# USART_IrDA.net
KiCad netlist of a schematic drawn in Altium Designer
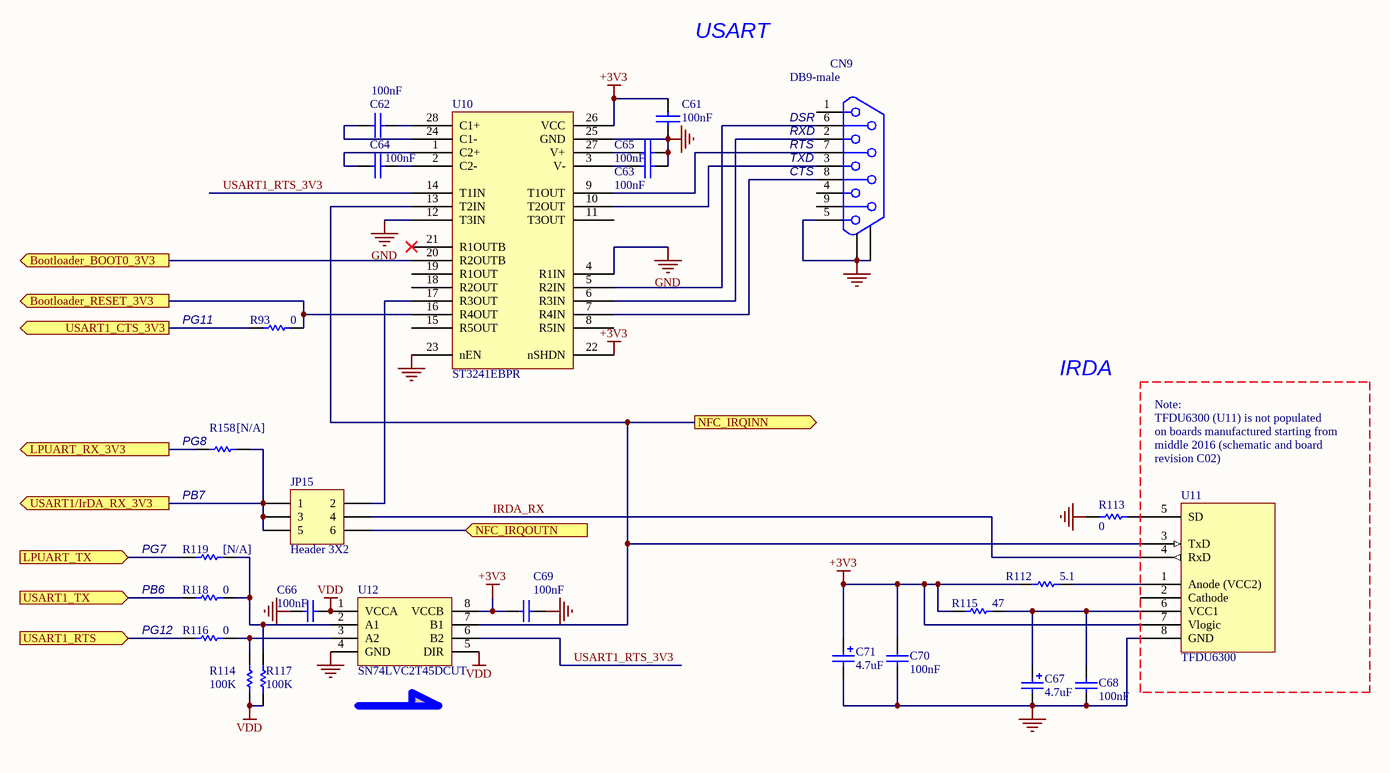
[diagram p0: USART_IrDA.SchDoc]

(export (version "E")
  (design (tool "Eeschema 10.0.6"))
  (components
    (comp (ref "C61")
      (value "100nF")
      (footprint "0402C")
      (description "Capacitor")
      (libsource (lib "*") (part "CAP"))
    )
    (comp (ref "C62")
      (value "100nF")
      (footprint "0402C")
      (description "Capacitor")
      (libsource (lib "*") (part "CAP"))
    )
    (comp (ref "C63")
      (value "100nF")
      (footprint "0402C")
      (description "Capacitor")
      (libsource (lib "*") (part "CAP"))
    )
    (comp (ref "C64")
      (value "100nF")
      (footprint "0402C")
      (description "Capacitor")
      (libsource (lib "*") (part "CAP"))
    )
    (comp (ref "C65")
      (value "100nF")
      (footprint "0402C")
      (description "Capacitor")
      (libsource (lib "*") (part "CAP"))
    )
    (comp (ref "C66")
      (value "100nF")
      (footprint "0402C")
      (description "Capacitor")
      (fields (field (name "PUBLISHER") "Altium Limited"))
      (libsource (lib "Miscellaneous Devices") (part "CAP"))
    )
    (comp (ref "C67")
      (value "4.7uF")
      (footprint "TAN-A")
      (description "Polarized Capacitor (Radial)")
      (fields (field (name "PUBLISHER") "Altium Limited"))
      (libsource (lib "Miscellaneous Devices") (part "Cap Pol1"))
    )
    (comp (ref "C68")
      (value "100nF")
      (footprint "0402C")
      (description "Capacitor")
      (fields (field (name "PUBLISHER") "Altium Limited"))
      (libsource (lib "Miscellaneous Devices") (part "CAP"))
    )
    (comp (ref "C69")
      (value "100nF")
      (footprint "0402C")
      (description "Capacitor")
      (fields (field (name "PUBLISHER") "Altium Limited"))
      (libsource (lib "Miscellaneous Devices") (part "CAP"))
    )
    (comp (ref "C70")
      (value "100nF")
      (footprint "0402C")
      (description "Capacitor")
      (fields (field (name "PUBLISHER") "Altium Limited"))
      (libsource (lib "Miscellaneous Devices") (part "CAP"))
    )
    (comp (ref "C71")
      (value "4.7uF")
      (footprint "TAN-A")
      (description "Polarized Capacitor (Radial)")
      (fields (field (name "PUBLISHER") "Altium Limited"))
      (libsource (lib "Miscellaneous Devices") (part "Cap Pol1"))
    )
    (comp (ref "CN9") (value "DB9-male") (footprint "DB9/M") (libsource (lib "MB1070") (part "DB9")))
    (comp (ref "JP15")
      (value "Header 3X2")
      (footprint "HDR_2X3_2R54")
      (description "Header, 3-Pin, Dual row")
      (fields (field (name "PUBLISHER") "Altium Limited"))
      (libsource (lib "Miscellaneous Connectors") (part "Header 3X2"))
    )
    (comp (ref "R93")
      (value "0")
      (footprint "0603R")
      (description "Resistor")
      (fields (field (name "PUBLISHER") "Altium Limited"))
      (libsource (lib "Miscellaneous Devices") (part "Res1"))
    )
    (comp (ref "R112")
      (value "5.1")
      (footprint "0402R")
      (description "Resistor")
      (fields (field (name "PUBLISHER") "Altium Limited"))
      (libsource (lib "Miscellaneous Devices") (part "Res1"))
    )
    (comp (ref "R113")
      (value "0")
      (footprint "0603R")
      (description "Resistor")
      (fields (field (name "PUBLISHER") "Altium Limited"))
      (libsource (lib "Miscellaneous Devices") (part "Res1"))
    )
    (comp (ref "R114")
      (value "100K")
      (footprint "0402R")
      (description "Resistor")
      (fields (field (name "PUBLISHER") "Altium Limited"))
      (libsource (lib "Miscellaneous Devices") (part "Res1"))
    )
    (comp (ref "R115")
      (value "47")
      (footprint "0402R")
      (description "Resistor")
      (fields (field (name "PUBLISHER") "Altium Limited"))
      (libsource (lib "Miscellaneous Devices") (part "Res1"))
    )
    (comp (ref "R116")
      (value "0")
      (footprint "0603R")
      (description "Resistor")
      (fields (field (name "PUBLISHER") "Altium Limited"))
      (libsource (lib "Miscellaneous Devices") (part "Res1"))
    )
    (comp (ref "R117")
      (value "100K")
      (footprint "0402R")
      (description "Resistor")
      (fields (field (name "PUBLISHER") "Altium Limited"))
      (libsource (lib "Miscellaneous Devices") (part "Res1"))
    )
    (comp (ref "R118")
      (value "0")
      (footprint "0603R")
      (description "Resistor")
      (fields (field (name "PUBLISHER") "Altium Limited"))
      (libsource (lib "Miscellaneous Devices") (part "Res1"))
    )
    (comp (ref "R119")
      (value "[N/A]")
      (footprint "0603R")
      (description "Resistor")
      (fields (field (name "PUBLISHER") "Altium Limited"))
      (libsource (lib "Miscellaneous Devices") (part "Res1"))
    )
    (comp (ref "R158")
      (value "[N/A]")
      (footprint "0603R")
      (description "Resistor")
      (fields (field (name "PUBLISHER") "Altium Limited"))
      (libsource (lib "Miscellaneous Devices") (part "Res1"))
    )
    (comp (ref "U10")
      (value "ST3241EBPR")
      (footprint "SSOP28_0R65_10R2X7R8")
      (libsource (lib "*") (part "ST3241"))
    )
    (comp (ref "U11") (value "TFDU6300") (footprint "IR_VISHAY3") (libsource (lib "*") (part "TFDU4300")))
    (comp (ref "U12")
      (value "SN74LVC2T45DCUT")
      (footprint "USOP8_0R5_2X3R1")
      (libsource (lib "MB818") (part "SN74LVC2T45DCUT"))
    )
  )
  (nets
    (net (code "1") (name "+3V3") (class "Default")
      (node (ref "C61") (pin "2") (pinfunction "2_2") (pintype "passive"))
      (node (ref "C69") (pin "2") (pinfunction "2_2") (pintype "passive"))
      (node (ref "C70") (pin "2") (pinfunction "2_2") (pintype "passive"))
      (node (ref "C71") (pin "1") (pinfunction "1_1") (pintype "passive"))
      (node (ref "R112") (pin "1") (pinfunction "1_1") (pintype "passive"))
      (node (ref "R115") (pin "1") (pinfunction "1_1") (pintype "passive"))
      (node (ref "U10") (pin "22") (pinfunction "nSHDN_22") (pintype "passive"))
      (node (ref "U10") (pin "26") (pinfunction "VCC_26") (pintype "passive"))
      (node (ref "U11") (pin "7") (pinfunction "Vlogic_7") (pintype "passive"))
      (node (ref "U12") (pin "8") (pinfunction "VCCB_8") (pintype "passive"))
    )
    (net (code "2") (name "/Bootloader_BOOT0_3V3") (class "Default")
      (node (ref "U10") (pin "20") (pinfunction "R2OUTB_20") (pintype "passive"))
    )
    (net (code "3") (name "/Bootloader_RESET_3V3") (class "Default")
      (node (ref "R93") (pin "1") (pinfunction "1_1") (pintype "passive"))
      (node (ref "U10") (pin "16") (pinfunction "R4OUT_16") (pintype "passive"))
    )
    (net (code "4") (name "/IRDA_RX") (class "Default")
      (node (ref "JP15") (pin "4") (pinfunction "4_4") (pintype "passive"))
      (node (ref "U11") (pin "4") (pinfunction "RxD_4") (pintype "output"))
    )
    (net (code "5") (name "/LPUART_RX_3V3") (class "Default")
      (node (ref "R158") (pin "2") (pinfunction "2_2") (pintype "passive"))
    )
    (net (code "6") (name "/LPUART_TX") (class "Default")
      (node (ref "R119") (pin "2") (pinfunction "2_2") (pintype "passive"))
    )
    (net (code "7") (name "/NFC_IRQINN") (class "Default")
      (node (ref "U10") (pin "13") (pinfunction "T2IN_13") (pintype "passive"))
      (node (ref "U11") (pin "3") (pinfunction "TxD_3") (pintype "input"))
      (node (ref "U12") (pin "7") (pinfunction "B1_7") (pintype "passive"))
    )
    (net (code "8") (name "/NFC_IRQOUTN") (class "Default")
      (node (ref "JP15") (pin "6") (pinfunction "6_6") (pintype "passive"))
    )
    (net (code "9") (name "/USART1_CTS_3V3") (class "Default")
      (node (ref "R93") (pin "2") (pinfunction "2_2") (pintype "passive"))
    )
    (net (code "10") (name "/USART1_RTS") (class "Default")
      (node (ref "R116") (pin "2") (pinfunction "2_2") (pintype "passive"))
    )
    (net (code "11") (name "/USART1_RTS_3V3") (class "Default")
      (node (ref "U10") (pin "14") (pinfunction "T1IN_14") (pintype "passive"))
      (node (ref "U12") (pin "6") (pinfunction "B2_6") (pintype "passive"))
    )
    (net (code "12") (name "/USART1_TX") (class "Default")
      (node (ref "R118") (pin "2") (pinfunction "2_2") (pintype "passive"))
    )
    (net (code "13") (name "/USART1{slash}IrDA_RX_3V3") (class "Default")
      (node (ref "JP15") (pin "1") (pinfunction "1_1") (pintype "passive"))
      (node (ref "JP15") (pin "3") (pinfunction "3_3") (pintype "passive"))
      (node (ref "JP15") (pin "5") (pinfunction "5_5") (pintype "passive"))
      (node (ref "R158") (pin "1") (pinfunction "1_1") (pintype "passive"))
    )
    (net (code "14") (name "GND") (class "Default")
      (node (ref "C61") (pin "1") (pinfunction "1_1") (pintype "passive"))
      (node (ref "C63") (pin "2") (pinfunction "2_2") (pintype "passive"))
      (node (ref "C65") (pin "2") (pinfunction "2_2") (pintype "passive"))
      (node (ref "C66") (pin "1") (pinfunction "1_1") (pintype "passive"))
      (node (ref "C67") (pin "2") (pinfunction "2_2") (pintype "passive"))
      (node (ref "C68") (pin "1") (pinfunction "1_1") (pintype "passive"))
      (node (ref "C69") (pin "1") (pinfunction "1_1") (pintype "passive"))
      (node (ref "C70") (pin "1") (pinfunction "1_1") (pintype "passive"))
      (node (ref "C71") (pin "2") (pinfunction "2_2") (pintype "passive"))
      (node (ref "CN9") (pin "10") (pinfunction "10_10") (pintype "passive"))
      (node (ref "CN9") (pin "11") (pinfunction "11_11") (pintype "passive"))
      (node (ref "CN9") (pin "5") (pinfunction "5_5") (pintype "passive"))
      (node (ref "R113") (pin "2") (pinfunction "2_2") (pintype "passive"))
      (node (ref "U10") (pin "12") (pinfunction "T3IN_12") (pintype "passive"))
      (node (ref "U10") (pin "23") (pinfunction "nEN_23") (pintype "passive"))
      (node (ref "U10") (pin "25") (pinfunction "GND_25") (pintype "passive"))
      (node (ref "U10") (pin "4") (pinfunction "R1IN_4") (pintype "passive"))
      (node (ref "U11") (pin "8") (pinfunction "GND_8") (pintype "passive"))
      (node (ref "U12") (pin "4") (pinfunction "GND_4") (pintype "passive"))
    )
    (net (code "15") (name "Net-(U10-C1+)") (class "Default")
      (node (ref "C62") (pin "2") (pinfunction "2_2") (pintype "passive"))
      (node (ref "U10") (pin "28") (pinfunction "C1+_28") (pintype "passive"))
    )
    (net (code "16") (name "Net-(U10-C1-)") (class "Default")
      (node (ref "C62") (pin "1") (pinfunction "1_1") (pintype "passive"))
      (node (ref "U10") (pin "24") (pinfunction "C1-_24") (pintype "passive"))
    )
    (net (code "17") (name "Net-(U10-C2+)") (class "Default")
      (node (ref "C64") (pin "1") (pinfunction "1_1") (pintype "passive"))
      (node (ref "U10") (pin "1") (pinfunction "C2+_1") (pintype "passive"))
    )
    (net (code "18") (name "Net-(U10-C2-)") (class "Default")
      (node (ref "C64") (pin "2") (pinfunction "2_2") (pintype "passive"))
      (node (ref "U10") (pin "2") (pinfunction "C2-_2") (pintype "passive"))
    )
    (net (code "19") (name "Net-(U10-R2IN)") (class "Default")
      (node (ref "CN9") (pin "6") (pinfunction "6_6") (pintype "passive"))
      (node (ref "U10") (pin "5") (pinfunction "R2IN_5") (pintype "passive"))
    )
    (net (code "20") (name "Net-(U10-R3IN)") (class "Default")
      (node (ref "CN9") (pin "2") (pinfunction "2_2") (pintype "passive"))
      (node (ref "U10") (pin "6") (pinfunction "R3IN_6") (pintype "passive"))
    )
    (net (code "21") (name "Net-(U10-R3OUT)") (class "Default")
      (node (ref "JP15") (pin "2") (pinfunction "2_2") (pintype "passive"))
      (node (ref "U10") (pin "17") (pinfunction "R3OUT_17") (pintype "passive"))
    )
    (net (code "22") (name "Net-(U10-R4IN)") (class "Default")
      (node (ref "CN9") (pin "8") (pinfunction "8_8") (pintype "passive"))
      (node (ref "U10") (pin "7") (pinfunction "R4IN_7") (pintype "passive"))
    )
    (net (code "23") (name "Net-(U10-T1OUT)") (class "Default")
      (node (ref "CN9") (pin "7") (pinfunction "7_7") (pintype "passive"))
      (node (ref "U10") (pin "9") (pinfunction "T1OUT_9") (pintype "passive"))
    )
    (net (code "24") (name "Net-(U10-T2OUT)") (class "Default")
      (node (ref "CN9") (pin "3") (pinfunction "3_3") (pintype "passive"))
      (node (ref "U10") (pin "10") (pinfunction "T2OUT_10") (pintype "passive"))
    )
    (net (code "25") (name "Net-(U10-V+)") (class "Default")
      (node (ref "C65") (pin "1") (pinfunction "1_1") (pintype "passive"))
      (node (ref "U10") (pin "27") (pinfunction "V+_27") (pintype "passive"))
    )
    (net (code "26") (name "Net-(U10-V-)") (class "Default")
      (node (ref "C63") (pin "1") (pinfunction "1_1") (pintype "passive"))
      (node (ref "U10") (pin "3") (pinfunction "V-_3") (pintype "passive"))
    )
    (net (code "27") (name "Net-(U11-Anode_(VCC2))") (class "Default")
      (node (ref "R112") (pin "2") (pinfunction "2_2") (pintype "passive"))
      (node (ref "U11") (pin "1") (pinfunction "Anode_(VCC2)_1") (pintype "passive"))
    )
    (net (code "28") (name "Net-(U11-SD)") (class "Default")
      (node (ref "R113") (pin "1") (pinfunction "1_1") (pintype "passive"))
      (node (ref "U11") (pin "5") (pinfunction "SD_5") (pintype "passive"))
    )
    (net (code "29") (name "Net-(U11-VCC1)") (class "Default")
      (node (ref "C67") (pin "1") (pinfunction "1_1") (pintype "passive"))
      (node (ref "C68") (pin "2") (pinfunction "2_2") (pintype "passive"))
      (node (ref "R115") (pin "2") (pinfunction "2_2") (pintype "passive"))
      (node (ref "U11") (pin "6") (pinfunction "VCC1_6") (pintype "passive"))
    )
    (net (code "30") (name "Net-(U12-A1)") (class "Default")
      (node (ref "R117") (pin "1") (pinfunction "1_1") (pintype "passive"))
      (node (ref "R118") (pin "1") (pinfunction "1_1") (pintype "passive"))
      (node (ref "R119") (pin "1") (pinfunction "1_1") (pintype "passive"))
      (node (ref "U12") (pin "2") (pinfunction "A1_2") (pintype "passive"))
    )
    (net (code "31") (name "Net-(U12-A2)") (class "Default")
      (node (ref "R114") (pin "1") (pinfunction "1_1") (pintype "passive"))
      (node (ref "R116") (pin "1") (pinfunction "1_1") (pintype "passive"))
      (node (ref "U12") (pin "3") (pinfunction "A2_3") (pintype "passive"))
    )
    (net (code "32") (name "VDD") (class "Default")
      (node (ref "C66") (pin "2") (pinfunction "2_2") (pintype "passive"))
      (node (ref "R114") (pin "2") (pinfunction "2_2") (pintype "passive"))
      (node (ref "R117") (pin "2") (pinfunction "2_2") (pintype "passive"))
      (node (ref "U12") (pin "1") (pinfunction "VCCA_1") (pintype "passive"))
      (node (ref "U12") (pin "5") (pinfunction "DIR_5") (pintype "passive"))
    )
    (net (code "33") (name "unconnected-(CN9-Pad1)") (class "Default")
      (node (ref "CN9") (pin "1") (pinfunction "1_1") (pintype "passive"))
    )
    (net (code "34") (name "unconnected-(CN9-Pad4)") (class "Default")
      (node (ref "CN9") (pin "4") (pinfunction "4_4") (pintype "passive"))
    )
    (net (code "35") (name "unconnected-(CN9-Pad9)") (class "Default")
      (node (ref "CN9") (pin "9") (pinfunction "9_9") (pintype "passive"))
    )
    (net (code "36") (name "unconnected-(U10-R1OUT-Pad19)") (class "Default")
      (node (ref "U10") (pin "19") (pinfunction "R1OUT_19") (pintype "passive"))
    )
    (net (code "37") (name "unconnected-(U10-R1OUTB-Pad21)") (class "Default")
      (node (ref "U10") (pin "21") (pinfunction "R1OUTB_21") (pintype "passive+no_connect"))
    )
    (net (code "38") (name "unconnected-(U10-R2OUT-Pad18)") (class "Default")
      (node (ref "U10") (pin "18") (pinfunction "R2OUT_18") (pintype "passive"))
    )
    (net (code "39") (name "unconnected-(U10-R5IN-Pad8)") (class "Default")
      (node (ref "U10") (pin "8") (pinfunction "R5IN_8") (pintype "passive"))
    )
    (net (code "40") (name "unconnected-(U10-R5OUT-Pad15)") (class "Default")
      (node (ref "U10") (pin "15") (pinfunction "R5OUT_15") (pintype "passive"))
    )
    (net (code "41") (name "unconnected-(U10-T3OUT-Pad11)") (class "Default")
      (node (ref "U10") (pin "11") (pinfunction "T3OUT_11") (pintype "passive"))
    )
    (net (code "42") (name "unconnected-(U11-Cathode-Pad2)") (class "Default")
      (node (ref "U11") (pin "2") (pinfunction "Cathode_2") (pintype "passive"))
    )
  )
)
